# Control_Logic.net
KiCad netlist of a schematic drawn in EasyEDA Pro
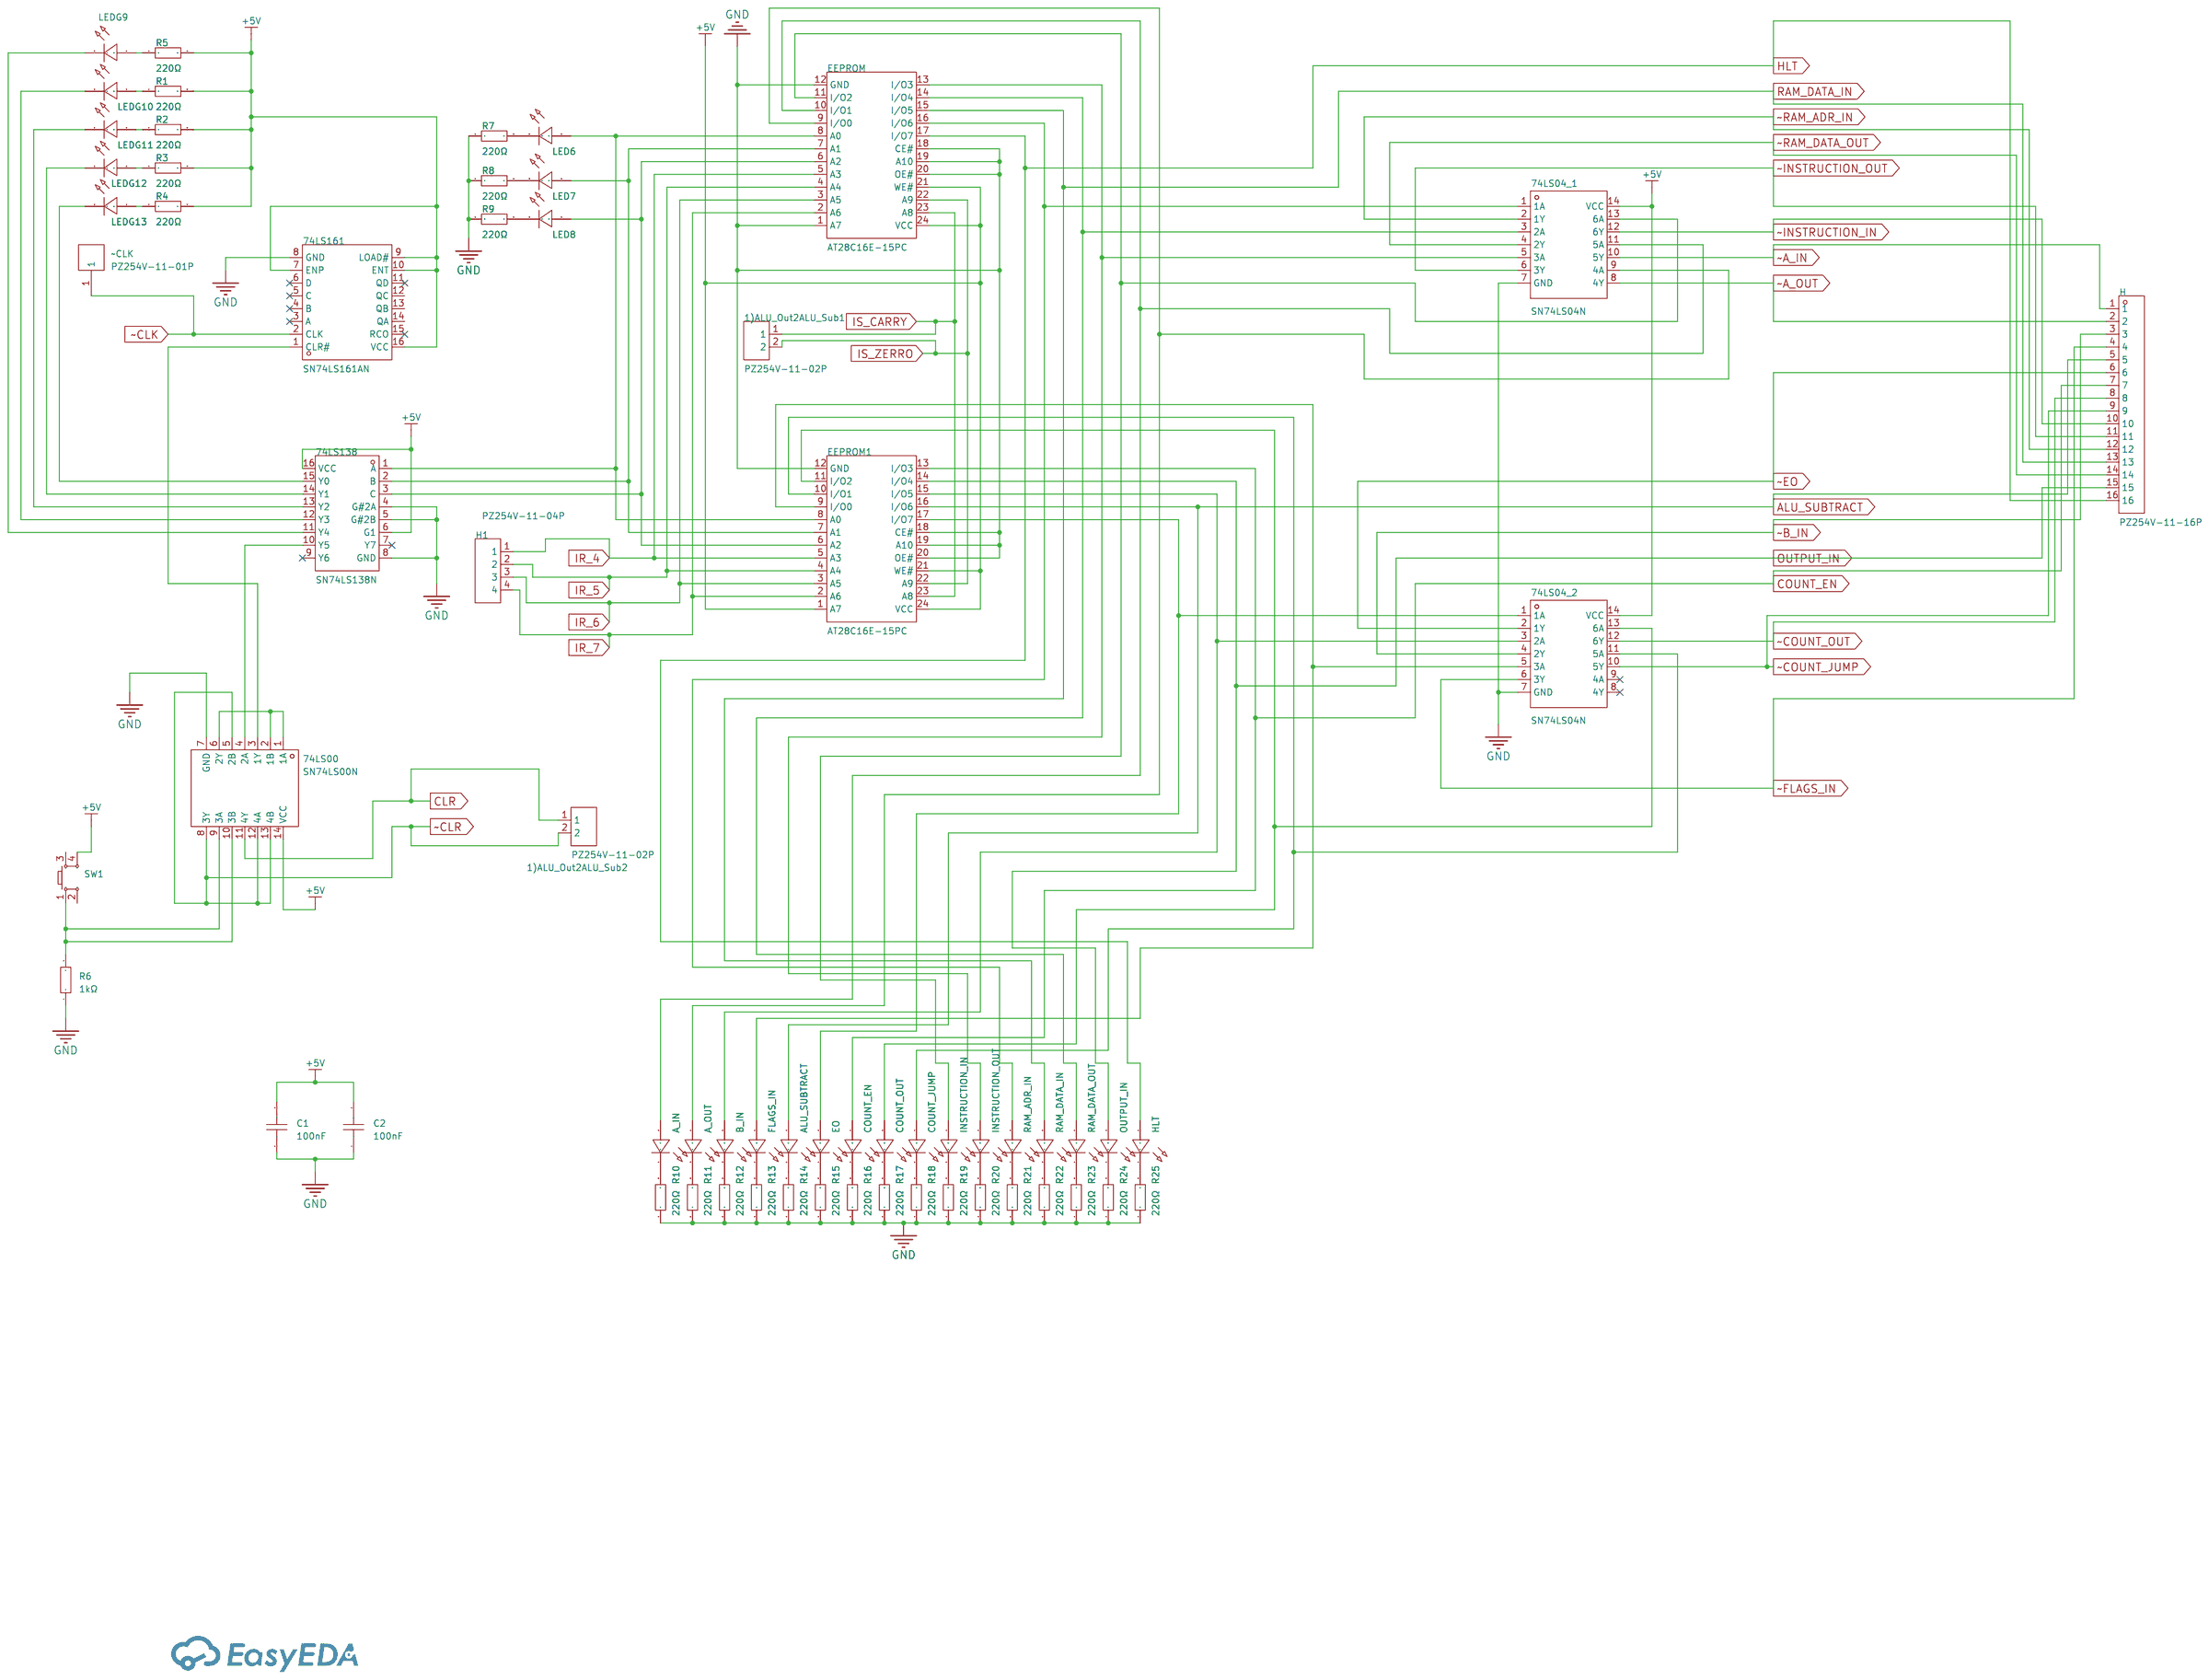
[diagram p0: schematic sheet]

(export (version "E")
  (design (tool "Eeschema 10.0.6"))
  (components
    (comp (ref "1)ALU_Out2ALU_Sub1")
      (value "PZ254V-11-02P")
      (footprint "easyedapro:HDR-TH_2P-P2.54-V-M")
      (fields (field (name "Manufacturer") "XFCN(兴飞)"))
      (libsource (lib "easyedapro") (part "PZ254V-11-02P"))
    )
    (comp (ref "1)ALU_Out2ALU_Sub2")
      (value "PZ254V-11-02P")
      (footprint "easyedapro:HDR-TH_2P-P2.54-V-M")
      (fields (field (name "Manufacturer") "XFCN(兴飞)"))
      (libsource (lib "easyedapro") (part "PZ254V-11-02P"))
    )
    (comp (ref "74LS00")
      (value "SN74LS00N")
      (footprint "easyedapro:PDIP-14_L19.7-W6.6-P2.54-LS8.3-BL")
      (fields (field (name "Manufacturer") "TI(德州仪器)"))
      (libsource (lib "easyedapro") (part "SN74LS00N"))
    )
    (comp (ref "74LS04_1")
      (value "SN74LS04N")
      (footprint "easyedapro:PDIP-14_L19.7-W6.6-P2.54-LS8.3-BL")
      (fields (field (name "Manufacturer") "TI(德州仪器)"))
      (libsource (lib "easyedapro") (part "SN74LS04N"))
    )
    (comp (ref "74LS04_2")
      (value "SN74LS04N")
      (footprint "easyedapro:PDIP-14_L19.7-W6.6-P2.54-LS8.3-BL")
      (fields (field (name "Manufacturer") "TI(德州仪器)"))
      (libsource (lib "easyedapro") (part "SN74LS04N"))
    )
    (comp (ref "74LS138")
      (value "SN74LS138N")
      (footprint "easyedapro:DIP-16_L19.8-W6.5-P2.54-LS7.6-BL")
      (fields (field (name "Manufacturer") "TI(德州仪器)"))
      (libsource (lib "easyedapro") (part "SN74LS138N"))
    )
    (comp (ref "74LS161")
      (value "SN74LS161AN")
      (footprint "easyedapro:PDIP-16_L19.3-W6.4-P2.54-LS7.9-BL")
      (fields (field (name "Manufacturer") "TI(德州仪器)"))
      (libsource (lib "easyedapro") (part "SN74LS161AN"))
    )
    (comp (ref "ALU_SUBTRACT")
      (value "~")
      (footprint "easyedapro:LED-TH_BD5.8-P2.54-FD")
      (libsource (lib "easyedapro") (part "LED_TH-R"))
    )
    (comp (ref "A_IN")
      (value "~")
      (footprint "easyedapro:LED-TH_BD5.8-P2.54-FD")
      (libsource (lib "easyedapro") (part "LED_TH-R"))
    )
    (comp (ref "A_OUT")
      (value "~")
      (footprint "easyedapro:LED-TH_BD5.8-P2.54-FD")
      (libsource (lib "easyedapro") (part "LED_TH-R"))
    )
    (comp (ref "B_IN")
      (value "~")
      (footprint "easyedapro:LED-TH_BD5.8-P2.54-FD")
      (libsource (lib "easyedapro") (part "LED_TH-R"))
    )
    (comp (ref "C1")
      (value "100nF")
      (footprint "easyedapro:CAP-TH_L8.5-W5.0-P5.00-D1.2")
      (fields (field (name "Manufacturer Part") "CT4-0805B104K500F3") (field (name "Manufacturer") "FH(风华)"))
      (libsource (lib "easyedapro") (part "CT4-0805B104K500F3"))
    )
    (comp (ref "C2")
      (value "100nF")
      (footprint "easyedapro:CAP-TH_L8.5-W5.0-P5.00-D1.2")
      (fields (field (name "Manufacturer Part") "CT4-0805B104K500F3") (field (name "Manufacturer") "FH(风华)"))
      (libsource (lib "easyedapro") (part "CT4-0805B104K500F3"))
    )
    (comp (ref "COUNT_EN")
      (value "~")
      (footprint "easyedapro:LED-TH_BD5.8-P2.54-FD")
      (libsource (lib "easyedapro") (part "LED_TH-R"))
    )
    (comp (ref "COUNT_JUMP")
      (value "~")
      (footprint "easyedapro:LED-TH_BD5.8-P2.54-FD")
      (libsource (lib "easyedapro") (part "LED_TH-R"))
    )
    (comp (ref "COUNT_OUT")
      (value "~")
      (footprint "easyedapro:LED-TH_BD5.8-P2.54-FD")
      (libsource (lib "easyedapro") (part "LED_TH-R"))
    )
    (comp (ref "EEPROM")
      (value "AT28C16E-15PC")
      (footprint "easyedapro:PDIP-24_L31.0-W13.5-P2.54-LS15.2-BL")
      (fields (field (name "Manufacturer") "MICROCHIP(美国微芯)"))
      (libsource (lib "easyedapro") (part "AT28C16E-15PC"))
    )
    (comp (ref "EEPROM1")
      (value "AT28C16E-15PC")
      (footprint "easyedapro:PDIP-24_L31.0-W13.5-P2.54-LS15.2-BL")
      (fields (field (name "Manufacturer") "MICROCHIP(美国微芯)"))
      (libsource (lib "easyedapro") (part "AT28C16E-15PC"))
    )
    (comp (ref "EO")
      (value "~")
      (footprint "easyedapro:LED-TH_BD5.8-P2.54-FD")
      (libsource (lib "easyedapro") (part "LED_TH-R"))
    )
    (comp (ref "FLAGS_IN")
      (value "~")
      (footprint "easyedapro:LED-TH_BD5.8-P2.54-FD")
      (libsource (lib "easyedapro") (part "LED_TH-R"))
    )
    (comp (ref "H")
      (value "PZ254V-11-16P")
      (footprint "easyedapro:HDR-TH_PZ254V-11-16P")
      (fields (field (name "Manufacturer") "XFCN(兴飞)"))
      (libsource (lib "easyedapro") (part "PZ254V-11-16P"))
    )
    (comp (ref "H1")
      (value "PZ254V-11-04P")
      (footprint "easyedapro:HDR-TH_4P-P2.54-V-M")
      (fields (field (name "Manufacturer") "XFCN(兴飞)"))
      (libsource (lib "easyedapro") (part "PZ254V-11-04P"))
    )
    (comp (ref "HLT")
      (value "~")
      (footprint "easyedapro:LED-TH_BD5.8-P2.54-FD")
      (libsource (lib "easyedapro") (part "LED_TH-R"))
    )
    (comp (ref "INSTRUCTION_IN")
      (value "~")
      (footprint "easyedapro:LED-TH_BD5.8-P2.54-FD")
      (libsource (lib "easyedapro") (part "LED_TH-R"))
    )
    (comp (ref "INSTRUCTION_OUT")
      (value "~")
      (footprint "easyedapro:LED-TH_BD5.8-P2.54-FD")
      (libsource (lib "easyedapro") (part "LED_TH-R"))
    )
    (comp (ref "LED6")
      (value "~")
      (footprint "easyedapro:LED-TH_BD5.8-P2.54-FD")
      (libsource (lib "easyedapro") (part "LED_TH-R"))
    )
    (comp (ref "LED7")
      (value "~")
      (footprint "easyedapro:LED-TH_BD5.8-P2.54-FD")
      (libsource (lib "easyedapro") (part "LED_TH-R"))
    )
    (comp (ref "LED8")
      (value "~")
      (footprint "easyedapro:LED-TH_BD5.8-P2.54-FD")
      (libsource (lib "easyedapro") (part "LED_TH-R"))
    )
    (comp (ref "LEDG9")
      (value "~")
      (footprint "easyedapro:LED-TH_BD5.8-P2.54-FD")
      (libsource (lib "easyedapro") (part "LED_TH-R"))
    )
    (comp (ref "LEDG10")
      (value "~")
      (footprint "easyedapro:LED-TH_BD5.8-P2.54-FD")
      (libsource (lib "easyedapro") (part "LED_TH-R"))
    )
    (comp (ref "LEDG11")
      (value "~")
      (footprint "easyedapro:LED-TH_BD5.8-P2.54-FD")
      (libsource (lib "easyedapro") (part "LED_TH-R"))
    )
    (comp (ref "LEDG12")
      (value "~")
      (footprint "easyedapro:LED-TH_BD5.8-P2.54-FD")
      (libsource (lib "easyedapro") (part "LED_TH-R"))
    )
    (comp (ref "LEDG13")
      (value "~")
      (footprint "easyedapro:LED-TH_BD5.8-P2.54-FD")
      (libsource (lib "easyedapro") (part "LED_TH-R"))
    )
    (comp (ref "OUTPUT_IN")
      (value "~")
      (footprint "easyedapro:LED-TH_BD5.8-P2.54-FD")
      (libsource (lib "easyedapro") (part "LED_TH-R"))
    )
    (comp (ref "R1")
      (value "220Ω")
      (footprint "easyedapro:R_AXIAL-0.4")
      (libsource (lib "easyedapro") (part "Res"))
    )
    (comp (ref "R2")
      (value "220Ω")
      (footprint "easyedapro:R_AXIAL-0.4")
      (libsource (lib "easyedapro") (part "Res"))
    )
    (comp (ref "R3")
      (value "220Ω")
      (footprint "easyedapro:R_AXIAL-0.4")
      (libsource (lib "easyedapro") (part "Res"))
    )
    (comp (ref "R4")
      (value "220Ω")
      (footprint "easyedapro:R_AXIAL-0.4")
      (libsource (lib "easyedapro") (part "Res"))
    )
    (comp (ref "R5")
      (value "220Ω")
      (footprint "easyedapro:R_AXIAL-0.4")
      (libsource (lib "easyedapro") (part "Res"))
    )
    (comp (ref "R6")
      (value "1kΩ")
      (footprint "easyedapro:R_AXIAL-0.4")
      (libsource (lib "easyedapro") (part "Res"))
    )
    (comp (ref "R7")
      (value "220Ω")
      (footprint "easyedapro:R_AXIAL-0.4")
      (libsource (lib "easyedapro") (part "Res"))
    )
    (comp (ref "R8")
      (value "220Ω")
      (footprint "easyedapro:R_AXIAL-0.4")
      (libsource (lib "easyedapro") (part "Res"))
    )
    (comp (ref "R9")
      (value "220Ω")
      (footprint "easyedapro:R_AXIAL-0.4")
      (libsource (lib "easyedapro") (part "Res"))
    )
    (comp (ref "R10")
      (value "220Ω")
      (footprint "easyedapro:R_AXIAL-0.4")
      (libsource (lib "easyedapro") (part "Res"))
    )
    (comp (ref "R11")
      (value "220Ω")
      (footprint "easyedapro:R_AXIAL-0.4")
      (libsource (lib "easyedapro") (part "Res"))
    )
    (comp (ref "R12")
      (value "220Ω")
      (footprint "easyedapro:R_AXIAL-0.4")
      (libsource (lib "easyedapro") (part "Res"))
    )
    (comp (ref "R13")
      (value "220Ω")
      (footprint "easyedapro:R_AXIAL-0.4")
      (libsource (lib "easyedapro") (part "Res"))
    )
    (comp (ref "R14")
      (value "220Ω")
      (footprint "easyedapro:R_AXIAL-0.4")
      (libsource (lib "easyedapro") (part "Res"))
    )
    (comp (ref "R15")
      (value "220Ω")
      (footprint "easyedapro:R_AXIAL-0.4")
      (libsource (lib "easyedapro") (part "Res"))
    )
    (comp (ref "R16")
      (value "220Ω")
      (footprint "easyedapro:R_AXIAL-0.4")
      (libsource (lib "easyedapro") (part "Res"))
    )
    (comp (ref "R17")
      (value "220Ω")
      (footprint "easyedapro:R_AXIAL-0.4")
      (libsource (lib "easyedapro") (part "Res"))
    )
    (comp (ref "R18")
      (value "220Ω")
      (footprint "easyedapro:R_AXIAL-0.4")
      (libsource (lib "easyedapro") (part "Res"))
    )
    (comp (ref "R19")
      (value "220Ω")
      (footprint "easyedapro:R_AXIAL-0.4")
      (libsource (lib "easyedapro") (part "Res"))
    )
    (comp (ref "R20")
      (value "220Ω")
      (footprint "easyedapro:R_AXIAL-0.4")
      (libsource (lib "easyedapro") (part "Res"))
    )
    (comp (ref "R21")
      (value "220Ω")
      (footprint "easyedapro:R_AXIAL-0.4")
      (libsource (lib "easyedapro") (part "Res"))
    )
    (comp (ref "R22")
      (value "220Ω")
      (footprint "easyedapro:R_AXIAL-0.4")
      (libsource (lib "easyedapro") (part "Res"))
    )
    (comp (ref "R23")
      (value "220Ω")
      (footprint "easyedapro:R_AXIAL-0.4")
      (libsource (lib "easyedapro") (part "Res"))
    )
    (comp (ref "R24")
      (value "220Ω")
      (footprint "easyedapro:R_AXIAL-0.4")
      (libsource (lib "easyedapro") (part "Res"))
    )
    (comp (ref "R25")
      (value "220Ω")
      (footprint "easyedapro:R_AXIAL-0.4")
      (libsource (lib "easyedapro") (part "Res"))
    )
    (comp (ref "RAM_ADR_IN")
      (value "~")
      (footprint "easyedapro:LED-TH_BD5.8-P2.54-FD")
      (libsource (lib "easyedapro") (part "LED_TH-R"))
    )
    (comp (ref "RAM_DATA_IN")
      (value "~")
      (footprint "easyedapro:LED-TH_BD5.8-P2.54-FD")
      (libsource (lib "easyedapro") (part "LED_TH-R"))
    )
    (comp (ref "RAM_DATA_OUT")
      (value "~")
      (footprint "easyedapro:LED-TH_BD5.8-P2.54-FD")
      (libsource (lib "easyedapro") (part "LED_TH-R"))
    )
    (comp (ref "SW1")
      (value "~")
      (footprint "easyedapro:KEY-TH_4P-L6.0-W6.0-P3.90-LS6.5")
      (libsource (lib "easyedapro") (part "轻触按键"))
    )
    (comp (ref "~CLK")
      (value "PZ254V-11-01P")
      (footprint "easyedapro:HDR-TH_1P-P2.54-V-M")
      (fields (field (name "Manufacturer") "XFCN(兴飞)"))
      (libsource (lib "easyedapro") (part "PZ254V-11-01P"))
    )
  )
  (nets
    (net (code "1") (name "+5V") (class "Default")
      (node (ref "74LS00") (pin "14") (pinfunction "VCC_14") (pintype "unspecified"))
      (node (ref "74LS04_1") (pin "14") (pinfunction "VCC_14") (pintype "unspecified"))
      (node (ref "74LS04_2") (pin "14") (pinfunction "VCC_14") (pintype "unspecified"))
      (node (ref "74LS138") (pin "16") (pinfunction "VCC_16") (pintype "input"))
      (node (ref "74LS138") (pin "6") (pinfunction "G1_6") (pintype "input"))
      (node (ref "74LS161") (pin "10") (pinfunction "ENT_10") (pintype "input"))
      (node (ref "74LS161") (pin "16") (pinfunction "VCC_16") (pintype "input"))
      (node (ref "74LS161") (pin "7") (pinfunction "ENP_7") (pintype "input"))
      (node (ref "74LS161") (pin "9") (pinfunction "LOAD#_9") (pintype "input"))
      (node (ref "C1") (pin "2") (pinfunction "2_2") (pintype "unspecified"))
      (node (ref "C2") (pin "2") (pinfunction "2_2") (pintype "unspecified"))
      (node (ref "EEPROM") (pin "21") (pinfunction "WE#_21") (pintype "unspecified"))
      (node (ref "EEPROM") (pin "24") (pinfunction "VCC_24") (pintype "unspecified"))
      (node (ref "EEPROM1") (pin "1") (pinfunction "A7_1") (pintype "unspecified"))
      (node (ref "EEPROM1") (pin "21") (pinfunction "WE#_21") (pintype "unspecified"))
      (node (ref "EEPROM1") (pin "24") (pinfunction "VCC_24") (pintype "unspecified"))
      (node (ref "R1") (pin "2") (pinfunction "2_2") (pintype "input"))
      (node (ref "R2") (pin "2") (pinfunction "2_2") (pintype "input"))
      (node (ref "R3") (pin "2") (pinfunction "2_2") (pintype "input"))
      (node (ref "R4") (pin "2") (pinfunction "2_2") (pintype "input"))
      (node (ref "R5") (pin "2") (pinfunction "2_2") (pintype "input"))
      (node (ref "SW1") (pin "4") (pinfunction "4_4") (pintype "input"))
    )
    (net (code "2") (name "ALU_SUBTRACT") (class "Default")
      (node (ref "ALU_SUBTRACT") (pin "1") (pinfunction "C_1") (pintype "input"))
      (node (ref "EEPROM1") (pin "16") (pinfunction "I/O6_16") (pintype "unspecified"))
      (node (ref "H") (pin "5") (pinfunction "5_5") (pintype "unspecified"))
    )
    (net (code "3") (name "CLR") (class "Default")
      (node (ref "1)ALU_Out2ALU_Sub2") (pin "1") (pinfunction "1_1") (pintype "unspecified"))
      (node (ref "74LS00") (pin "11") (pinfunction "4Y_11") (pintype "unspecified"))
    )
    (net (code "4") (name "COUNT_EN") (class "Default")
      (node (ref "COUNT_EN") (pin "1") (pinfunction "C_1") (pintype "input"))
      (node (ref "EEPROM1") (pin "13") (pinfunction "I/O3_13") (pintype "unspecified"))
      (node (ref "H") (pin "7") (pinfunction "7_7") (pintype "unspecified"))
    )
    (net (code "5") (name "GND") (class "Default")
      (node (ref "74LS00") (pin "7") (pinfunction "GND_7") (pintype "unspecified"))
      (node (ref "74LS04_1") (pin "7") (pinfunction "GND_7") (pintype "unspecified"))
      (node (ref "74LS04_2") (pin "7") (pinfunction "GND_7") (pintype "unspecified"))
      (node (ref "74LS138") (pin "4") (pinfunction "G#2A_4") (pintype "input"))
      (node (ref "74LS138") (pin "5") (pinfunction "G#2B_5") (pintype "input"))
      (node (ref "74LS138") (pin "8") (pinfunction "GND_8") (pintype "input"))
      (node (ref "74LS161") (pin "8") (pinfunction "GND_8") (pintype "input"))
      (node (ref "C1") (pin "1") (pinfunction "1_1") (pintype "unspecified"))
      (node (ref "C2") (pin "1") (pinfunction "1_1") (pintype "unspecified"))
      (node (ref "EEPROM") (pin "1") (pinfunction "A7_1") (pintype "unspecified"))
      (node (ref "EEPROM") (pin "12") (pinfunction "GND_12") (pintype "unspecified"))
      (node (ref "EEPROM") (pin "18") (pinfunction "CE#_18") (pintype "unspecified"))
      (node (ref "EEPROM") (pin "19") (pinfunction "A10_19") (pintype "unspecified"))
      (node (ref "EEPROM") (pin "20") (pinfunction "OE#_20") (pintype "unspecified"))
      (node (ref "EEPROM1") (pin "12") (pinfunction "GND_12") (pintype "unspecified"))
      (node (ref "EEPROM1") (pin "18") (pinfunction "CE#_18") (pintype "unspecified"))
      (node (ref "EEPROM1") (pin "19") (pinfunction "A10_19") (pintype "unspecified"))
      (node (ref "EEPROM1") (pin "20") (pinfunction "OE#_20") (pintype "unspecified"))
      (node (ref "R10") (pin "1") (pinfunction "1_1") (pintype "input"))
      (node (ref "R11") (pin "1") (pinfunction "1_1") (pintype "input"))
      (node (ref "R12") (pin "1") (pinfunction "1_1") (pintype "input"))
      (node (ref "R13") (pin "1") (pinfunction "1_1") (pintype "input"))
      (node (ref "R14") (pin "1") (pinfunction "1_1") (pintype "input"))
      (node (ref "R15") (pin "1") (pinfunction "1_1") (pintype "input"))
      (node (ref "R16") (pin "1") (pinfunction "1_1") (pintype "input"))
      (node (ref "R17") (pin "1") (pinfunction "1_1") (pintype "input"))
      (node (ref "R18") (pin "1") (pinfunction "1_1") (pintype "input"))
      (node (ref "R19") (pin "1") (pinfunction "1_1") (pintype "input"))
      (node (ref "R20") (pin "1") (pinfunction "1_1") (pintype "input"))
      (node (ref "R21") (pin "1") (pinfunction "1_1") (pintype "input"))
      (node (ref "R22") (pin "1") (pinfunction "1_1") (pintype "input"))
      (node (ref "R23") (pin "1") (pinfunction "1_1") (pintype "input"))
      (node (ref "R24") (pin "1") (pinfunction "1_1") (pintype "input"))
      (node (ref "R25") (pin "1") (pinfunction "1_1") (pintype "input"))
      (node (ref "R6") (pin "1") (pinfunction "1_1") (pintype "input"))
      (node (ref "R7") (pin "1") (pinfunction "1_1") (pintype "input"))
      (node (ref "R8") (pin "1") (pinfunction "1_1") (pintype "input"))
      (node (ref "R9") (pin "1") (pinfunction "1_1") (pintype "input"))
    )
    (net (code "6") (name "HLT") (class "Default")
      (node (ref "EEPROM") (pin "17") (pinfunction "I/O7_17") (pintype "unspecified"))
      (node (ref "H") (pin "16") (pinfunction "16_16") (pintype "unspecified"))
      (node (ref "HLT") (pin "1") (pinfunction "C_1") (pintype "input"))
    )
    (net (code "7") (name "IR_4") (class "Default")
      (node (ref "EEPROM") (pin "5") (pinfunction "A3_5") (pintype "unspecified"))
      (node (ref "EEPROM1") (pin "5") (pinfunction "A3_5") (pintype "unspecified"))
      (node (ref "H1") (pin "1") (pinfunction "1_1") (pintype "unspecified"))
    )
    (net (code "8") (name "IR_5") (class "Default")
      (node (ref "EEPROM") (pin "4") (pinfunction "A4_4") (pintype "unspecified"))
      (node (ref "EEPROM1") (pin "4") (pinfunction "A4_4") (pintype "unspecified"))
      (node (ref "H1") (pin "2") (pinfunction "2_2") (pintype "unspecified"))
    )
    (net (code "9") (name "IR_6") (class "Default")
      (node (ref "EEPROM") (pin "3") (pinfunction "A5_3") (pintype "unspecified"))
      (node (ref "EEPROM1") (pin "3") (pinfunction "A5_3") (pintype "unspecified"))
      (node (ref "H1") (pin "3") (pinfunction "3_3") (pintype "unspecified"))
    )
    (net (code "10") (name "IR_7") (class "Default")
      (node (ref "EEPROM") (pin "2") (pinfunction "A6_2") (pintype "unspecified"))
      (node (ref "EEPROM1") (pin "2") (pinfunction "A6_2") (pintype "unspecified"))
      (node (ref "H1") (pin "4") (pinfunction "4_4") (pintype "unspecified"))
    )
    (net (code "11") (name "IS_CARRY") (class "Default")
      (node (ref "1)ALU_Out2ALU_Sub1") (pin "1") (pinfunction "1_1") (pintype "unspecified"))
      (node (ref "EEPROM") (pin "23") (pinfunction "A8_23") (pintype "unspecified"))
      (node (ref "EEPROM1") (pin "23") (pinfunction "A8_23") (pintype "unspecified"))
    )
    (net (code "12") (name "IS_ZERRO") (class "Default")
      (node (ref "1)ALU_Out2ALU_Sub1") (pin "2") (pinfunction "2_2") (pintype "unspecified"))
      (node (ref "EEPROM") (pin "22") (pinfunction "A9_22") (pintype "unspecified"))
      (node (ref "EEPROM1") (pin "22") (pinfunction "A9_22") (pintype "unspecified"))
    )
    (net (code "13") (name "Net-(74LS00-1A)") (class "Default")
      (node (ref "74LS00") (pin "1") (pinfunction "1A_1") (pintype "unspecified"))
      (node (ref "74LS00") (pin "2") (pinfunction "1B_2") (pintype "unspecified"))
      (node (ref "74LS00") (pin "6") (pinfunction "2Y_6") (pintype "unspecified"))
    )
    (net (code "14") (name "Net-(74LS00-1Y)") (class "Default")
      (node (ref "74LS00") (pin "3") (pinfunction "1Y_3") (pintype "unspecified"))
      (node (ref "74LS161") (pin "1") (pinfunction "CLR#_1") (pintype "input"))
    )
    (net (code "15") (name "Net-(74LS00-2A)") (class "Default")
      (node (ref "74LS00") (pin "4") (pinfunction "2A_4") (pintype "unspecified"))
      (node (ref "74LS138") (pin "10") (pinfunction "Y5_10") (pintype "input"))
    )
    (net (code "16") (name "Net-(74LS00-3A)") (class "Default")
      (node (ref "74LS00") (pin "10") (pinfunction "3B_10") (pintype "unspecified"))
      (node (ref "74LS00") (pin "9") (pinfunction "3A_9") (pintype "unspecified"))
      (node (ref "R6") (pin "2") (pinfunction "2_2") (pintype "input"))
      (node (ref "SW1") (pin "1") (pinfunction "1_1") (pintype "input"))
    )
    (net (code "17") (name "Net-(74LS04_1-1A)") (class "Default")
      (node (ref "74LS04_1") (pin "1") (pinfunction "1A_1") (pintype "unspecified"))
      (node (ref "EEPROM") (pin "16") (pinfunction "I/O6_16") (pintype "unspecified"))
      (node (ref "RAM_ADR_IN") (pin "1") (pinfunction "C_1") (pintype "input"))
    )
    (net (code "18") (name "Net-(74LS04_1-2A)") (class "Default")
      (node (ref "74LS04_1") (pin "3") (pinfunction "2A_3") (pintype "unspecified"))
      (node (ref "EEPROM") (pin "14") (pinfunction "I/O4_14") (pintype "unspecified"))
      (node (ref "RAM_DATA_OUT") (pin "1") (pinfunction "C_1") (pintype "input"))
    )
    (net (code "19") (name "Net-(74LS04_1-3A)") (class "Default")
      (node (ref "74LS04_1") (pin "5") (pinfunction "3A_5") (pintype "unspecified"))
      (node (ref "EEPROM") (pin "13") (pinfunction "I/O3_13") (pintype "unspecified"))
      (node (ref "INSTRUCTION_OUT") (pin "1") (pinfunction "C_1") (pintype "input"))
    )
    (net (code "20") (name "Net-(74LS04_1-4A)") (class "Default")
      (node (ref "74LS04_1") (pin "9") (pinfunction "4A_9") (pintype "unspecified"))
      (node (ref "A_OUT") (pin "1") (pinfunction "C_1") (pintype "input"))
      (node (ref "EEPROM") (pin "9") (pinfunction "I/O0_9") (pintype "unspecified"))
    )
    (net (code "21") (name "Net-(74LS04_1-5A)") (class "Default")
      (node (ref "74LS04_1") (pin "11") (pinfunction "5A_11") (pintype "unspecified"))
      (node (ref "A_IN") (pin "1") (pinfunction "C_1") (pintype "input"))
      (node (ref "EEPROM") (pin "10") (pinfunction "I/O1_10") (pintype "unspecified"))
    )
    (net (code "22") (name "Net-(74LS04_1-6A)") (class "Default")
      (node (ref "74LS04_1") (pin "13") (pinfunction "6A_13") (pintype "unspecified"))
      (node (ref "EEPROM") (pin "11") (pinfunction "I/O2_11") (pintype "unspecified"))
      (node (ref "INSTRUCTION_IN") (pin "1") (pinfunction "C_1") (pintype "input"))
    )
    (net (code "23") (name "Net-(74LS04_2-1A)") (class "Default")
      (node (ref "74LS04_2") (pin "1") (pinfunction "1A_1") (pintype "unspecified"))
      (node (ref "EEPROM1") (pin "17") (pinfunction "I/O7_17") (pintype "unspecified"))
      (node (ref "EO") (pin "1") (pinfunction "C_1") (pintype "input"))
    )
    (net (code "24") (name "Net-(74LS04_2-2A)") (class "Default")
      (node (ref "74LS04_2") (pin "3") (pinfunction "2A_3") (pintype "unspecified"))
      (node (ref "B_IN") (pin "1") (pinfunction "C_1") (pintype "input"))
      (node (ref "EEPROM1") (pin "15") (pinfunction "I/O5_15") (pintype "unspecified"))
    )
    (net (code "25") (name "Net-(74LS04_2-3A)") (class "Default")
      (node (ref "74LS04_2") (pin "5") (pinfunction "3A_5") (pintype "unspecified"))
      (node (ref "EEPROM1") (pin "9") (pinfunction "I/O0_9") (pintype "unspecified"))
      (node (ref "FLAGS_IN") (pin "1") (pinfunction "C_1") (pintype "input"))
    )
    (net (code "26") (name "Net-(74LS04_2-5A)") (class "Default")
      (node (ref "74LS04_2") (pin "11") (pinfunction "5A_11") (pintype "unspecified"))
      (node (ref "COUNT_JUMP") (pin "1") (pinfunction "C_1") (pintype "input"))
      (node (ref "EEPROM1") (pin "10") (pinfunction "I/O1_10") (pintype "unspecified"))
    )
    (net (code "27") (name "Net-(74LS04_2-6A)") (class "Default")
      (node (ref "74LS04_2") (pin "13") (pinfunction "6A_13") (pintype "unspecified"))
      (node (ref "COUNT_OUT") (pin "1") (pinfunction "C_1") (pintype "input"))
      (node (ref "EEPROM1") (pin "11") (pinfunction "I/O2_11") (pintype "unspecified"))
    )
    (net (code "28") (name "Net-(74LS138-A)") (class "Default")
      (node (ref "74LS138") (pin "1") (pinfunction "A_1") (pintype "input"))
      (node (ref "EEPROM") (pin "8") (pinfunction "A0_8") (pintype "unspecified"))
      (node (ref "EEPROM1") (pin "8") (pinfunction "A0_8") (pintype "unspecified"))
      (node (ref "LED6") (pin "1") (pinfunction "C_1") (pintype "input"))
    )
    (net (code "29") (name "Net-(74LS138-B)") (class "Default")
      (node (ref "74LS138") (pin "2") (pinfunction "B_2") (pintype "input"))
      (node (ref "EEPROM") (pin "7") (pinfunction "A1_7") (pintype "unspecified"))
      (node (ref "EEPROM1") (pin "7") (pinfunction "A1_7") (pintype "unspecified"))
      (node (ref "LED7") (pin "1") (pinfunction "C_1") (pintype "input"))
    )
    (net (code "30") (name "Net-(74LS138-C)") (class "Default")
      (node (ref "74LS138") (pin "3") (pinfunction "C_3") (pintype "input"))
      (node (ref "EEPROM") (pin "6") (pinfunction "A2_6") (pintype "unspecified"))
      (node (ref "EEPROM1") (pin "6") (pinfunction "A2_6") (pintype "unspecified"))
      (node (ref "LED8") (pin "1") (pinfunction "C_1") (pintype "input"))
    )
    (net (code "31") (name "Net-(74LS138-Y0)") (class "Default")
      (node (ref "74LS138") (pin "15") (pinfunction "Y0_15") (pintype "input"))
      (node (ref "LEDG13") (pin "2") (pinfunction "A_2") (pintype "input"))
    )
    (net (code "32") (name "Net-(74LS138-Y1)") (class "Default")
      (node (ref "74LS138") (pin "14") (pinfunction "Y1_14") (pintype "input"))
      (node (ref "LEDG12") (pin "2") (pinfunction "A_2") (pintype "input"))
    )
    (net (code "33") (name "Net-(74LS138-Y2)") (class "Default")
      (node (ref "74LS138") (pin "13") (pinfunction "Y2_13") (pintype "input"))
      (node (ref "LEDG11") (pin "2") (pinfunction "A_2") (pintype "input"))
    )
    (net (code "34") (name "Net-(74LS138-Y3)") (class "Default")
      (node (ref "74LS138") (pin "12") (pinfunction "Y3_12") (pintype "input"))
      (node (ref "LEDG10") (pin "2") (pinfunction "A_2") (pintype "input"))
    )
    (net (code "35") (name "Net-(74LS138-Y4)") (class "Default")
      (node (ref "74LS138") (pin "11") (pinfunction "Y4_11") (pintype "input"))
      (node (ref "LEDG9") (pin "2") (pinfunction "A_2") (pintype "input"))
    )
    (net (code "36") (name "Net-(ALU_SUBTRACT-A)") (class "Default")
      (node (ref "ALU_SUBTRACT") (pin "2") (pinfunction "A_2") (pintype "input"))
      (node (ref "R14") (pin "2") (pinfunction "2_2") (pintype "input"))
    )
    (net (code "37") (name "Net-(A_IN-A)") (class "Default")
      (node (ref "A_IN") (pin "2") (pinfunction "A_2") (pintype "input"))
      (node (ref "R10") (pin "2") (pinfunction "2_2") (pintype "input"))
    )
    (net (code "38") (name "Net-(A_OUT-A)") (class "Default")
      (node (ref "A_OUT") (pin "2") (pinfunction "A_2") (pintype "input"))
      (node (ref "R11") (pin "2") (pinfunction "2_2") (pintype "input"))
    )
    (net (code "39") (name "Net-(B_IN-A)") (class "Default")
      (node (ref "B_IN") (pin "2") (pinfunction "A_2") (pintype "input"))
      (node (ref "R12") (pin "2") (pinfunction "2_2") (pintype "input"))
    )
    (net (code "40") (name "Net-(COUNT_EN-A)") (class "Default")
      (node (ref "COUNT_EN") (pin "2") (pinfunction "A_2") (pintype "input"))
      (node (ref "R16") (pin "2") (pinfunction "2_2") (pintype "input"))
    )
    (net (code "41") (name "Net-(COUNT_JUMP-A)") (class "Default")
      (node (ref "COUNT_JUMP") (pin "2") (pinfunction "A_2") (pintype "input"))
      (node (ref "R18") (pin "2") (pinfunction "2_2") (pintype "input"))
    )
    (net (code "42") (name "Net-(COUNT_OUT-A)") (class "Default")
      (node (ref "COUNT_OUT") (pin "2") (pinfunction "A_2") (pintype "input"))
      (node (ref "R17") (pin "2") (pinfunction "2_2") (pintype "input"))
    )
    (net (code "43") (name "Net-(EO-A)") (class "Default")
      (node (ref "EO") (pin "2") (pinfunction "A_2") (pintype "input"))
      (node (ref "R15") (pin "2") (pinfunction "2_2") (pintype "input"))
    )
    (net (code "44") (name "Net-(FLAGS_IN-A)") (class "Default")
      (node (ref "FLAGS_IN") (pin "2") (pinfunction "A_2") (pintype "input"))
      (node (ref "R13") (pin "2") (pinfunction "2_2") (pintype "input"))
    )
    (net (code "45") (name "Net-(HLT-A)") (class "Default")
      (node (ref "HLT") (pin "2") (pinfunction "A_2") (pintype "input"))
      (node (ref "R25") (pin "2") (pinfunction "2_2") (pintype "input"))
    )
    (net (code "46") (name "Net-(INSTRUCTION_IN-A)") (class "Default")
      (node (ref "INSTRUCTION_IN") (pin "2") (pinfunction "A_2") (pintype "input"))
      (node (ref "R19") (pin "2") (pinfunction "2_2") (pintype "input"))
    )
    (net (code "47") (name "Net-(INSTRUCTION_OUT-A)") (class "Default")
      (node (ref "INSTRUCTION_OUT") (pin "2") (pinfunction "A_2") (pintype "input"))
      (node (ref "R20") (pin "2") (pinfunction "2_2") (pintype "input"))
    )
    (net (code "48") (name "Net-(LED6-A)") (class "Default")
      (node (ref "LED6") (pin "2") (pinfunction "A_2") (pintype "input"))
      (node (ref "R7") (pin "2") (pinfunction "2_2") (pintype "input"))
    )
    (net (code "49") (name "Net-(LED7-A)") (class "Default")
      (node (ref "LED7") (pin "2") (pinfunction "A_2") (pintype "input"))
      (node (ref "R8") (pin "2") (pinfunction "2_2") (pintype "input"))
    )
    (net (code "50") (name "Net-(LED8-A)") (class "Default")
      (node (ref "LED8") (pin "2") (pinfunction "A_2") (pintype "input"))
      (node (ref "R9") (pin "2") (pinfunction "2_2") (pintype "input"))
    )
    (net (code "51") (name "Net-(LEDG9-C)") (class "Default")
      (node (ref "LEDG9") (pin "1") (pinfunction "C_1") (pintype "input"))
      (node (ref "R5") (pin "1") (pinfunction "1_1") (pintype "input"))
    )
    (net (code "52") (name "Net-(LEDG10-C)") (class "Default")
      (node (ref "LEDG10") (pin "1") (pinfunction "C_1") (pintype "input"))
      (node (ref "R1") (pin "1") (pinfunction "1_1") (pintype "input"))
    )
    (net (code "53") (name "Net-(LEDG11-C)") (class "Default")
      (node (ref "LEDG11") (pin "1") (pinfunction "C_1") (pintype "input"))
      (node (ref "R2") (pin "1") (pinfunction "1_1") (pintype "input"))
    )
    (net (code "54") (name "Net-(LEDG12-C)") (class "Default")
      (node (ref "LEDG12") (pin "1") (pinfunction "C_1") (pintype "input"))
      (node (ref "R3") (pin "1") (pinfunction "1_1") (pintype "input"))
    )
    (net (code "55") (name "Net-(LEDG13-C)") (class "Default")
      (node (ref "LEDG13") (pin "1") (pinfunction "C_1") (pintype "input"))
      (node (ref "R4") (pin "1") (pinfunction "1_1") (pintype "input"))
    )
    (net (code "56") (name "Net-(OUTPUT_IN-A)") (class "Default")
      (node (ref "OUTPUT_IN") (pin "2") (pinfunction "A_2") (pintype "input"))
      (node (ref "R24") (pin "2") (pinfunction "2_2") (pintype "input"))
    )
    (net (code "57") (name "Net-(RAM_ADR_IN-A)") (class "Default")
      (node (ref "R21") (pin "2") (pinfunction "2_2") (pintype "input"))
      (node (ref "RAM_ADR_IN") (pin "2") (pinfunction "A_2") (pintype "input"))
    )
    (net (code "58") (name "Net-(RAM_DATA_IN-A)") (class "Default")
      (node (ref "R22") (pin "2") (pinfunction "2_2") (pintype "input"))
      (node (ref "RAM_DATA_IN") (pin "2") (pinfunction "A_2") (pintype "input"))
    )
    (net (code "59") (name "Net-(RAM_DATA_OUT-A)") (class "Default")
      (node (ref "R23") (pin "2") (pinfunction "2_2") (pintype "input"))
      (node (ref "RAM_DATA_OUT") (pin "2") (pinfunction "A_2") (pintype "input"))
    )
    (net (code "60") (name "OUTPUT_IN") (class "Default")
      (node (ref "EEPROM1") (pin "14") (pinfunction "I/O4_14") (pintype "unspecified"))
      (node (ref "H") (pin "15") (pinfunction "15_15") (pintype "unspecified"))
      (node (ref "OUTPUT_IN") (pin "1") (pinfunction "C_1") (pintype "input"))
    )
    (net (code "61") (name "RAM_DATA_IN") (class "Default")
      (node (ref "EEPROM") (pin "15") (pinfunction "I/O5_15") (pintype "unspecified"))
      (node (ref "H") (pin "13") (pinfunction "13_13") (pintype "unspecified"))
      (node (ref "RAM_DATA_IN") (pin "1") (pinfunction "C_1") (pintype "input"))
    )
    (net (code "62") (name "unconnected-(74LS04_2-4A-Pad9)") (class "Default")
      (node (ref "74LS04_2") (pin "9") (pinfunction "4A_9") (pintype "unspecified+no_connect"))
    )
    (net (code "63") (name "unconnected-(74LS04_2-4Y-Pad8)") (class "Default")
      (node (ref "74LS04_2") (pin "8") (pinfunction "4Y_8") (pintype "unspecified+no_connect"))
    )
    (net (code "64") (name "unconnected-(74LS138-Y6-Pad9)") (class "Default")
      (node (ref "74LS138") (pin "9") (pinfunction "Y6_9") (pintype "input+no_connect"))
    )
    (net (code "65") (name "unconnected-(74LS138-Y7-Pad7)") (class "Default")
      (node (ref "74LS138") (pin "7") (pinfunction "Y7_7") (pintype "input+no_connect"))
    )
    (net (code "66") (name "unconnected-(74LS161-A-Pad3)") (class "Default")
      (node (ref "74LS161") (pin "3") (pinfunction "A_3") (pintype "input+no_connect"))
    )
    (net (code "67") (name "unconnected-(74LS161-B-Pad4)") (class "Default")
      (node (ref "74LS161") (pin "4") (pinfunction "B_4") (pintype "input+no_connect"))
    )
    (net (code "68") (name "unconnected-(74LS161-C-Pad5)") (class "Default")
      (node (ref "74LS161") (pin "5") (pinfunction "C_5") (pintype "input+no_connect"))
    )
    (net (code "69") (name "unconnected-(74LS161-D-Pad6)") (class "Default")
      (node (ref "74LS161") (pin "6") (pinfunction "D_6") (pintype "input+no_connect"))
    )
    (net (code "70") (name "unconnected-(74LS161-QA-Pad14)") (class "Default")
      (node (ref "74LS161") (pin "14") (pinfunction "QA_14") (pintype "input"))
    )
    (net (code "71") (name "unconnected-(74LS161-QB-Pad13)") (class "Default")
      (node (ref "74LS161") (pin "13") (pinfunction "QB_13") (pintype "input"))
    )
    (net (code "72") (name "unconnected-(74LS161-QC-Pad12)") (class "Default")
      (node (ref "74LS161") (pin "12") (pinfunction "QC_12") (pintype "input"))
    )
    (net (code "73") (name "unconnected-(74LS161-QD-Pad11)") (class "Default")
      (node (ref "74LS161") (pin "11") (pinfunction "QD_11") (pintype "input+no_connect"))
    )
    (net (code "74") (name "unconnected-(74LS161-RCO-Pad15)") (class "Default")
      (node (ref "74LS161") (pin "15") (pinfunction "RCO_15") (pintype "input+no_connect"))
    )
    (net (code "75") (name "unconnected-(SW1-Pad2)") (class "Default")
      (node (ref "SW1") (pin "2") (pinfunction "2_2") (pintype "input"))
    )
    (net (code "76") (name "unconnected-(SW1-Pad3)") (class "Default")
      (node (ref "SW1") (pin "3") (pinfunction "3_3") (pintype "input"))
    )
    (net (code "77") (name "~A_IN") (class "Default")
      (node (ref "74LS04_1") (pin "10") (pinfunction "5Y_10") (pintype "unspecified"))
      (node (ref "H") (pin "1") (pinfunction "1_1") (pintype "unspecified"))
    )
    (net (code "78") (name "~A_OUT") (class "Default")
      (node (ref "74LS04_1") (pin "8") (pinfunction "4Y_8") (pintype "unspecified"))
      (node (ref "H") (pin "2") (pinfunction "2_2") (pintype "unspecified"))
    )
    (net (code "79") (name "~B_IN") (class "Default")
      (node (ref "74LS04_2") (pin "4") (pinfunction "2Y_4") (pintype "unspecified"))
      (node (ref "H") (pin "3") (pinfunction "3_3") (pintype "unspecified"))
    )
    (net (code "80") (name "~CLK") (class "Default")
      (node (ref "74LS161") (pin "2") (pinfunction "CLK_2") (pintype "input"))
      (node (ref "~CLK") (pin "1") (pinfunction "1_1") (pintype "unspecified"))
    )
    (net (code "81") (name "~CLR") (class "Default")
      (node (ref "1)ALU_Out2ALU_Sub2") (pin "2") (pinfunction "2_2") (pintype "unspecified"))
      (node (ref "74LS00") (pin "12") (pinfunction "4A_12") (pintype "unspecified"))
      (node (ref "74LS00") (pin "13") (pinfunction "4B_13") (pintype "unspecified"))
      (node (ref "74LS00") (pin "5") (pinfunction "2B_5") (pintype "unspecified"))
      (node (ref "74LS00") (pin "8") (pinfunction "3Y_8") (pintype "unspecified"))
    )
    (net (code "82") (name "~COUNT_JUMP") (class "Default")
      (node (ref "74LS04_2") (pin "10") (pinfunction "5Y_10") (pintype "unspecified"))
      (node (ref "H") (pin "9") (pinfunction "9_9") (pintype "unspecified"))
    )
    (net (code "83") (name "~COUNT_OUT") (class "Default")
      (node (ref "74LS04_2") (pin "12") (pinfunction "6Y_12") (pintype "unspecified"))
      (node (ref "H") (pin "8") (pinfunction "8_8") (pintype "unspecified"))
    )
    (net (code "84") (name "~EO") (class "Default")
      (node (ref "74LS04_2") (pin "2") (pinfunction "1Y_2") (pintype "unspecified"))
      (node (ref "H") (pin "6") (pinfunction "6_6") (pintype "unspecified"))
    )
    (net (code "85") (name "~FLAGS_IN") (class "Default")
      (node (ref "74LS04_2") (pin "6") (pinfunction "3Y_6") (pintype "unspecified"))
      (node (ref "H") (pin "4") (pinfunction "4_4") (pintype "unspecified"))
    )
    (net (code "86") (name "~INSTRUCTION_IN") (class "Default")
      (node (ref "74LS04_1") (pin "12") (pinfunction "6Y_12") (pintype "unspecified"))
      (node (ref "H") (pin "10") (pinfunction "10_10") (pintype "unspecified"))
    )
    (net (code "87") (name "~INSTRUCTION_OUT") (class "Default")
      (node (ref "74LS04_1") (pin "6") (pinfunction "3Y_6") (pintype "unspecified"))
      (node (ref "H") (pin "11") (pinfunction "11_11") (pintype "unspecified"))
    )
    (net (code "88") (name "~RAM_ADR_IN") (class "Default")
      (node (ref "74LS04_1") (pin "2") (pinfunction "1Y_2") (pintype "unspecified"))
      (node (ref "H") (pin "12") (pinfunction "12_12") (pintype "unspecified"))
    )
    (net (code "89") (name "~RAM_DATA_OUT") (class "Default")
      (node (ref "74LS04_1") (pin "4") (pinfunction "2Y_4") (pintype "unspecified"))
      (node (ref "H") (pin "14") (pinfunction "14_14") (pintype "unspecified"))
    )
  )
)
